# EEG-RM_151117P01.net
KiCad netlist of a schematic drawn in EAGLE
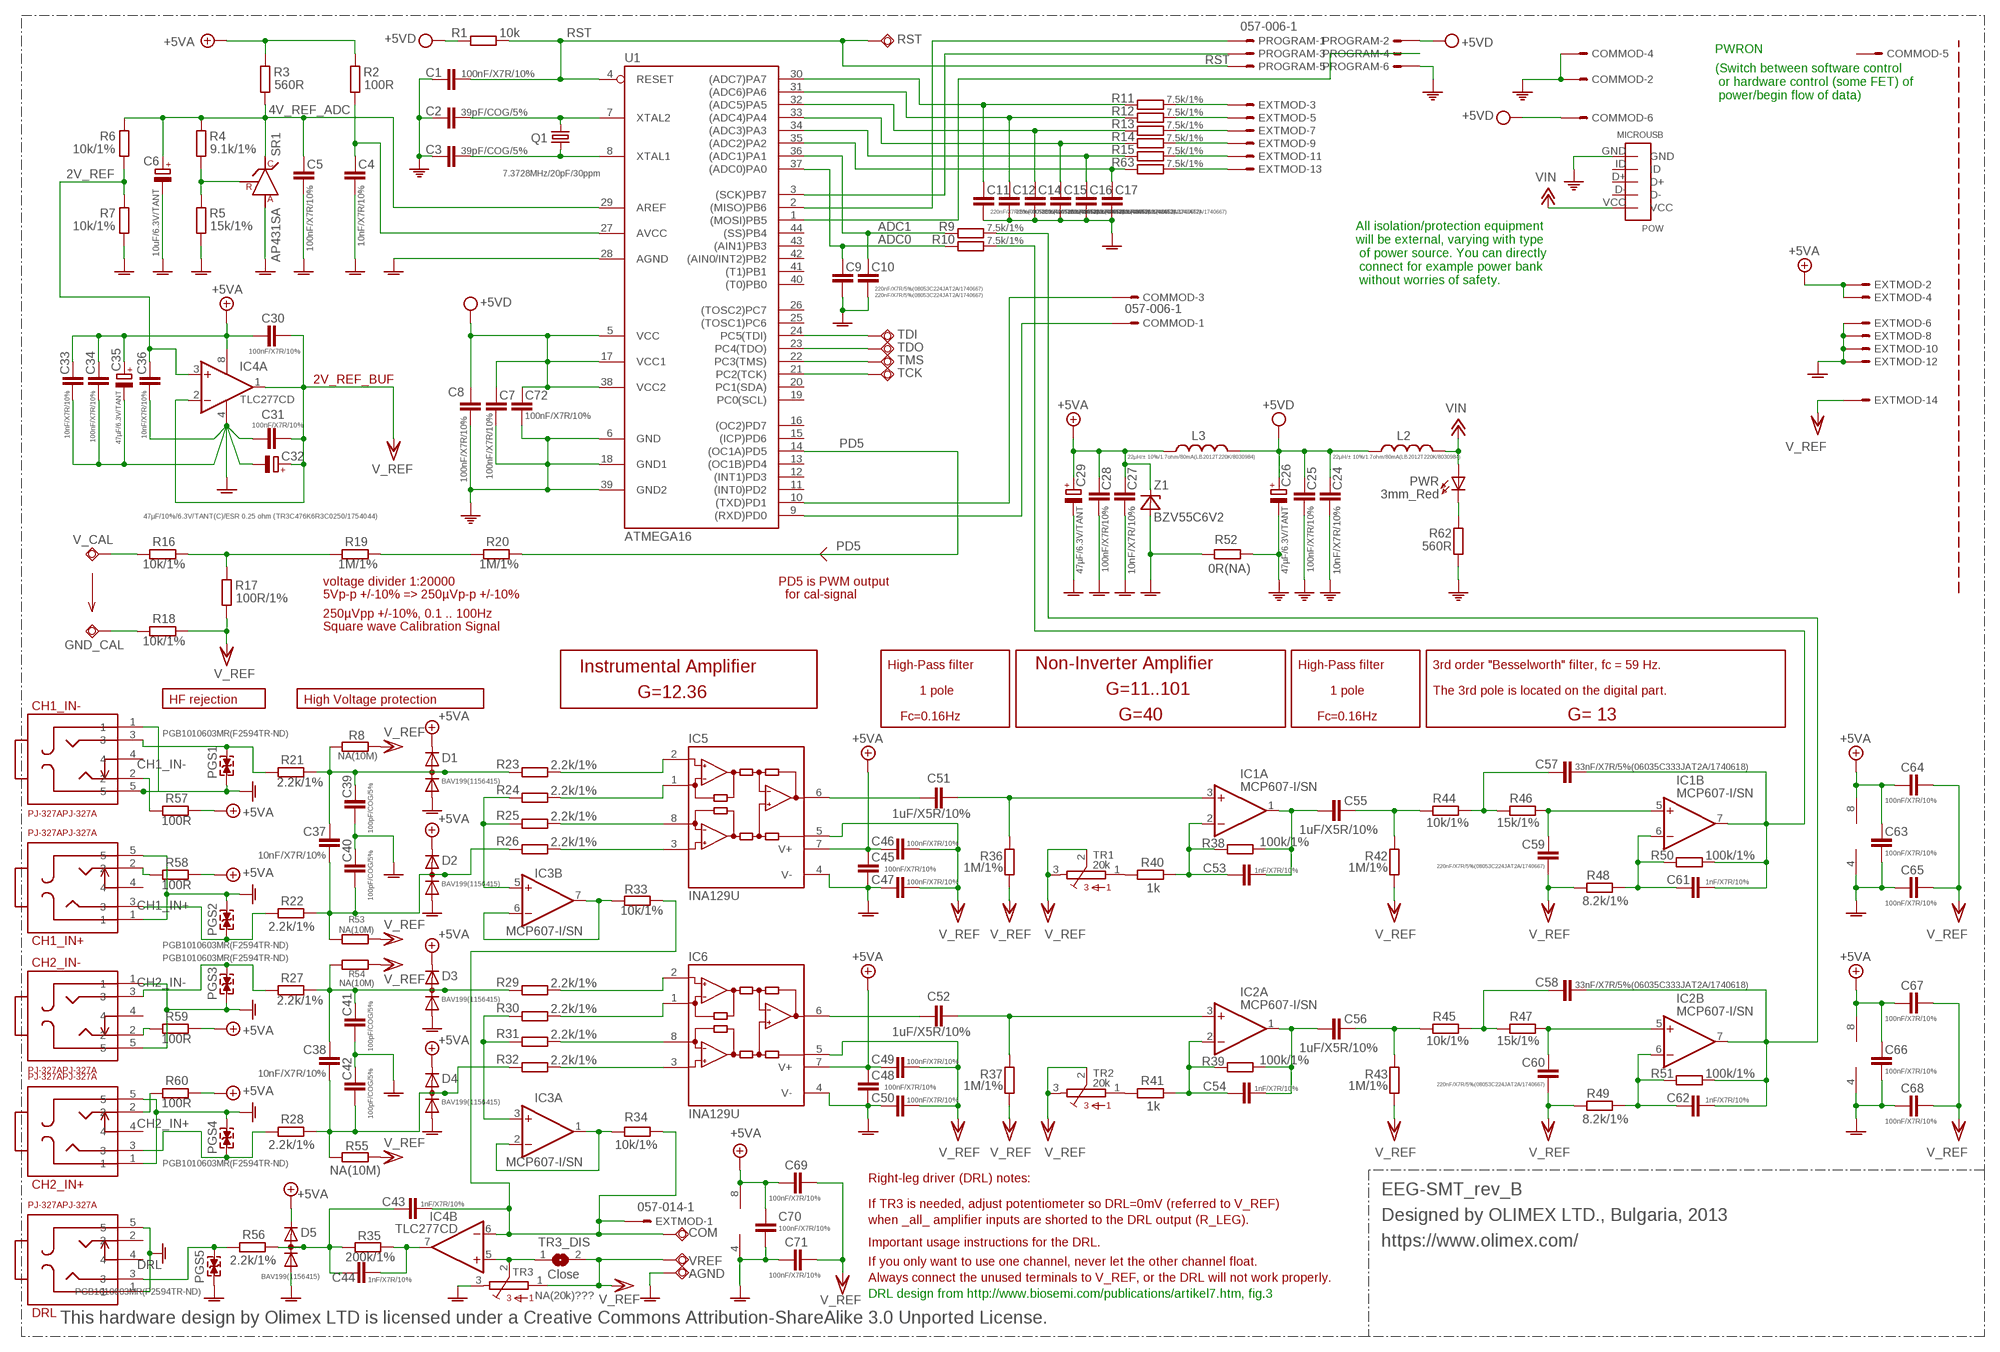
[diagram p0: schematic, sheet 1]

(export (version "E")
  (design (tool "Eeschema 10.0.6"))
  (components
    (comp (ref "AGND")
      (value "TESTPAD3")
      (footprint "eagle-import:TEST_PAD40_70_SQUARE")
      (libsource (lib "eagle-import") (part "TESTPAD3"))
    )
    (comp (ref "C1")
      (value "100nF/X7R/10%")
      (footprint "eagle-import:C2012")
      (libsource (lib "eagle-import") (part "C-EUC2012"))
    )
    (comp (ref "C2")
      (value "39pF/COG/5%")
      (footprint "eagle-import:C2012")
      (libsource (lib "eagle-import") (part "C-EUC2012"))
    )
    (comp (ref "C3")
      (value "39pF/COG/5%")
      (footprint "eagle-import:C2012")
      (libsource (lib "eagle-import") (part "C-EUC2012"))
    )
    (comp (ref "C4")
      (value "10nF/X7R/10%")
      (footprint "eagle-import:C2012")
      (libsource (lib "eagle-import") (part "C-EUC2012"))
    )
    (comp (ref "C5")
      (value "100nF/X7R/10%")
      (footprint "eagle-import:C2012")
      (libsource (lib "eagle-import") (part "C-EUC2012"))
    )
    (comp (ref "C6")
      (value "10uF/6.3V/TANT")
      (footprint "eagle-import:CT3216")
      (libsource (lib "eagle-import") (part "CPOL-EUCT3216"))
    )
    (comp (ref "C7")
      (value "100nF/X7R/10%")
      (footprint "eagle-import:C2012")
      (libsource (lib "eagle-import") (part "C-EUC2012"))
    )
    (comp (ref "C8")
      (value "100nF/X7R/10%")
      (footprint "eagle-import:C2012")
      (libsource (lib "eagle-import") (part "C-EUC2012"))
    )
    (comp (ref "C9")
      (value "220nF/X7R/5%(08053C224JAT2A/1740667)")
      (footprint "eagle-import:C2012")
      (libsource (lib "eagle-import") (part "C-EUC2012"))
    )
    (comp (ref "C10")
      (value "220nF/X7R/5%(08053C224JAT2A/1740667)")
      (footprint "eagle-import:C2012")
      (libsource (lib "eagle-import") (part "C-EUC2012"))
    )
    (comp (ref "C11")
      (value "220nF/X7R/5%(08053C224JAT2A/1740667)")
      (footprint "eagle-import:C2012")
      (libsource (lib "eagle-import") (part "C-EUC2012"))
    )
    (comp (ref "C12")
      (value "220nF/X7R/5%(08053C224JAT2A/1740667)")
      (footprint "eagle-import:C2012")
      (libsource (lib "eagle-import") (part "C-EUC2012"))
    )
    (comp (ref "C14")
      (value "220nF/X7R/5%(08053C224JAT2A/1740667)")
      (footprint "eagle-import:C2012")
      (libsource (lib "eagle-import") (part "C-EUC2012"))
    )
    (comp (ref "C15")
      (value "220nF/X7R/5%(08053C224JAT2A/1740667)")
      (footprint "eagle-import:C2012")
      (libsource (lib "eagle-import") (part "C-EUC2012"))
    )
    (comp (ref "C16")
      (value "220nF/X7R/5%(08053C224JAT2A/1740667)")
      (footprint "eagle-import:C2012")
      (libsource (lib "eagle-import") (part "C-EUC2012"))
    )
    (comp (ref "C17")
      (value "220nF/X7R/5%(08053C224JAT2A/1740667)")
      (footprint "eagle-import:C2012")
      (libsource (lib "eagle-import") (part "C-EUC2012"))
    )
    (comp (ref "C24")
      (value "10nF/X7R/10%")
      (footprint "eagle-import:C2012")
      (libsource (lib "eagle-import") (part "C-EUC2012"))
    )
    (comp (ref "C25")
      (value "100nF/X7R/10%")
      (footprint "eagle-import:C2012")
      (libsource (lib "eagle-import") (part "C-EUC2012"))
    )
    (comp (ref "C26")
      (value "47µF/6.3V/TANT")
      (footprint "eagle-import:CT3528")
      (libsource (lib "eagle-import") (part "CPOL-EUCT3528"))
    )
    (comp (ref "C27")
      (value "10nF/X7R/10%")
      (footprint "eagle-import:C2012")
      (libsource (lib "eagle-import") (part "C-EUC2012"))
    )
    (comp (ref "C28")
      (value "100nF/X7R/10%")
      (footprint "eagle-import:C2012")
      (libsource (lib "eagle-import") (part "C-EUC2012"))
    )
    (comp (ref "C29")
      (value "47µF/6.3V/TANT")
      (footprint "eagle-import:CT3528")
      (libsource (lib "eagle-import") (part "CPOL-EUCT3528"))
    )
    (comp (ref "C30")
      (value "100nF/X7R/10%")
      (footprint "eagle-import:C2012")
      (libsource (lib "eagle-import") (part "C-EUC2012"))
    )
    (comp (ref "C31")
      (value "100nF/X7R/10%")
      (footprint "eagle-import:C2012")
      (libsource (lib "eagle-import") (part "C-EUC2012"))
    )
    (comp (ref "C32")
      (value "47µF/10%/6.3V/TANT(C)/ESR 0.25 ohm (TR3C476K6R3C0250/1754044)")
      (footprint "eagle-import:CT6032")
      (libsource (lib "eagle-import") (part "CPOL-EUCT6032"))
    )
    (comp (ref "C33")
      (value "10nF/X7R/10%")
      (footprint "eagle-import:C2012")
      (libsource (lib "eagle-import") (part "C-EUC2012"))
    )
    (comp (ref "C34")
      (value "100nF/X7R/10%")
      (footprint "eagle-import:C2012")
      (libsource (lib "eagle-import") (part "C-EUC2012"))
    )
    (comp (ref "C35")
      (value "47µF/6.3V/TANT")
      (footprint "eagle-import:CT3528")
      (libsource (lib "eagle-import") (part "CPOL-EUCT3528"))
    )
    (comp (ref "C36")
      (value "10nF/X7R/10%")
      (footprint "eagle-import:C2012")
      (libsource (lib "eagle-import") (part "C-EUC2012"))
    )
    (comp (ref "C37")
      (value "10nF/X7R/10%")
      (footprint "eagle-import:C2012")
      (libsource (lib "eagle-import") (part "C-EUC2012"))
    )
    (comp (ref "C38")
      (value "10nF/X7R/10%")
      (footprint "eagle-import:C2012")
      (libsource (lib "eagle-import") (part "C-EUC2012"))
    )
    (comp (ref "C39")
      (value "100pF/COG/5%")
      (footprint "eagle-import:C2012")
      (libsource (lib "eagle-import") (part "C-EUC2012"))
    )
    (comp (ref "C40")
      (value "100pF/COG/5%")
      (footprint "eagle-import:C2012")
      (libsource (lib "eagle-import") (part "C-EUC2012"))
    )
    (comp (ref "C41")
      (value "100pF/COG/5%")
      (footprint "eagle-import:C2012")
      (libsource (lib "eagle-import") (part "C-EUC2012"))
    )
    (comp (ref "C42")
      (value "100pF/COG/5%")
      (footprint "eagle-import:C2012")
      (libsource (lib "eagle-import") (part "C-EUC2012"))
    )
    (comp (ref "C43")
      (value "1nF/X7R/10%")
      (footprint "eagle-import:C2012")
      (libsource (lib "eagle-import") (part "C-EUC2012"))
    )
    (comp (ref "C44")
      (value "1nF/X7R/10%")
      (footprint "eagle-import:C2012")
      (libsource (lib "eagle-import") (part "C-EUC2012"))
    )
    (comp (ref "C45")
      (value "100nF/X7R/10%")
      (footprint "eagle-import:C2012")
      (libsource (lib "eagle-import") (part "C-EUC2012"))
    )
    (comp (ref "C46")
      (value "100nF/X7R/10%")
      (footprint "eagle-import:C2012")
      (libsource (lib "eagle-import") (part "C-EUC2012"))
    )
    (comp (ref "C47")
      (value "100nF/X7R/10%")
      (footprint "eagle-import:C2012")
      (libsource (lib "eagle-import") (part "C-EUC2012"))
    )
    (comp (ref "C48")
      (value "100nF/X7R/10%")
      (footprint "eagle-import:C2012")
      (libsource (lib "eagle-import") (part "C-EUC2012"))
    )
    (comp (ref "C49")
      (value "100nF/X7R/10%")
      (footprint "eagle-import:C2012")
      (libsource (lib "eagle-import") (part "C-EUC2012"))
    )
    (comp (ref "C50")
      (value "100nF/X7R/10%")
      (footprint "eagle-import:C2012")
      (libsource (lib "eagle-import") (part "C-EUC2012"))
    )
    (comp (ref "C51")
      (value "1uF/X5R/10%")
      (footprint "eagle-import:C2012")
      (libsource (lib "eagle-import") (part "C-EUC2012"))
    )
    (comp (ref "C52")
      (value "1uF/X5R/10%")
      (footprint "eagle-import:C2012")
      (libsource (lib "eagle-import") (part "C-EUC2012"))
    )
    (comp (ref "C53")
      (value "1nF/X7R/10%")
      (footprint "eagle-import:C2012")
      (libsource (lib "eagle-import") (part "C-EUC2012"))
    )
    (comp (ref "C54")
      (value "1nF/X7R/10%")
      (footprint "eagle-import:C2012")
      (libsource (lib "eagle-import") (part "C-EUC2012"))
    )
    (comp (ref "C55")
      (value "1uF/X5R/10%")
      (footprint "eagle-import:C2012")
      (libsource (lib "eagle-import") (part "C-EUC2012"))
    )
    (comp (ref "C56")
      (value "1uF/X5R/10%")
      (footprint "eagle-import:C2012")
      (libsource (lib "eagle-import") (part "C-EUC2012"))
    )
    (comp (ref "C57")
      (value "33nF/X7R/5%(06035C333JAT2A/1740618)")
      (footprint "eagle-import:C2012")
      (libsource (lib "eagle-import") (part "C-EUC2012"))
    )
    (comp (ref "C58")
      (value "33nF/X7R/5%(06035C333JAT2A/1740618)")
      (footprint "eagle-import:C2012")
      (libsource (lib "eagle-import") (part "C-EUC2012"))
    )
    (comp (ref "C59")
      (value "220nF/X7R/5%(08053C224JAT2A/1740667)")
      (footprint "eagle-import:C2012")
      (libsource (lib "eagle-import") (part "C-EUC2012"))
    )
    (comp (ref "C60")
      (value "220nF/X7R/5%(08053C224JAT2A/1740667)")
      (footprint "eagle-import:C2012")
      (libsource (lib "eagle-import") (part "C-EUC2012"))
    )
    (comp (ref "C61")
      (value "1nF/X7R/10%")
      (footprint "eagle-import:C2012")
      (libsource (lib "eagle-import") (part "C-EUC2012"))
    )
    (comp (ref "C62")
      (value "1nF/X7R/10%")
      (footprint "eagle-import:C2012")
      (libsource (lib "eagle-import") (part "C-EUC2012"))
    )
    (comp (ref "C63")
      (value "100nF/X7R/10%")
      (footprint "eagle-import:C2012")
      (libsource (lib "eagle-import") (part "C-EUC2012"))
    )
    (comp (ref "C64")
      (value "100nF/X7R/10%")
      (footprint "eagle-import:C2012")
      (libsource (lib "eagle-import") (part "C-EUC2012"))
    )
    (comp (ref "C65")
      (value "100nF/X7R/10%")
      (footprint "eagle-import:C2012")
      (libsource (lib "eagle-import") (part "C-EUC2012"))
    )
    (comp (ref "C66")
      (value "100nF/X7R/10%")
      (footprint "eagle-import:C2012")
      (libsource (lib "eagle-import") (part "C-EUC2012"))
    )
    (comp (ref "C67")
      (value "100nF/X7R/10%")
      (footprint "eagle-import:C2012")
      (libsource (lib "eagle-import") (part "C-EUC2012"))
    )
    (comp (ref "C68")
      (value "100nF/X7R/10%")
      (footprint "eagle-import:C2012")
      (libsource (lib "eagle-import") (part "C-EUC2012"))
    )
    (comp (ref "C69")
      (value "100nF/X7R/10%")
      (footprint "eagle-import:C2012")
      (libsource (lib "eagle-import") (part "C-EUC2012"))
    )
    (comp (ref "C70")
      (value "100nF/X7R/10%")
      (footprint "eagle-import:C2012")
      (libsource (lib "eagle-import") (part "C-EUC2012"))
    )
    (comp (ref "C71")
      (value "100nF/X7R/10%")
      (footprint "eagle-import:C2012")
      (libsource (lib "eagle-import") (part "C-EUC2012"))
    )
    (comp (ref "C72")
      (value "100nF/X7R/10%")
      (footprint "eagle-import:C2012")
      (libsource (lib "eagle-import") (part "C-EUC2012"))
    )
    (comp (ref "CH1_IN+")
      (value "PJ-327APJ-327A")
      (footprint "eagle-import:PJ-327A")
      (libsource (lib "eagle-import") (part "PJ-327APJ-327A"))
    )
    (comp (ref "CH1_IN-")
      (value "PJ-327APJ-327A")
      (footprint "eagle-import:PJ-327A")
      (libsource (lib "eagle-import") (part "PJ-327APJ-327A"))
    )
    (comp (ref "CH2_IN+")
      (value "PJ-327APJ-327A")
      (footprint "eagle-import:PJ-327A")
      (libsource (lib "eagle-import") (part "PJ-327APJ-327A"))
    )
    (comp (ref "CH2_IN-")
      (value "PJ-327APJ-327A")
      (footprint "eagle-import:PJ-327A")
      (libsource (lib "eagle-import") (part "PJ-327APJ-327A"))
    )
    (comp (ref "COM")
      (value "TESTPAD3")
      (footprint "eagle-import:TEST_PAD40_70_SQUARE")
      (libsource (lib "eagle-import") (part "TESTPAD3"))
    )
    (comp (ref "COMMOD")
      (value "057-006-1")
      (footprint "eagle-import:057-006-1")
      (libsource (lib "eagle-import") (part "057-006-1"))
    )
    (comp (ref "D1")
      (value "BAV199(1156415)")
      (footprint "eagle-import:SOT23C(BAT54S)")
      (libsource (lib "eagle-import") (part "DIODE_AC-AC_"))
    )
    (comp (ref "D2")
      (value "BAV199(1156415)")
      (footprint "eagle-import:SOT23C(BAT54S)")
      (libsource (lib "eagle-import") (part "DIODE_AC-AC_"))
    )
    (comp (ref "D3")
      (value "BAV199(1156415)")
      (footprint "eagle-import:SOT23C(BAT54S)")
      (libsource (lib "eagle-import") (part "DIODE_AC-AC_"))
    )
    (comp (ref "D4")
      (value "BAV199(1156415)")
      (footprint "eagle-import:SOT23C(BAT54S)")
      (libsource (lib "eagle-import") (part "DIODE_AC-AC_"))
    )
    (comp (ref "D5")
      (value "BAV199(1156415)")
      (footprint "eagle-import:SOT23C(BAT54S)")
      (libsource (lib "eagle-import") (part "DIODE_AC-AC_"))
    )
    (comp (ref "DRL")
      (value "PJ-327APJ-327A")
      (footprint "eagle-import:PJ-327A")
      (libsource (lib "eagle-import") (part "PJ-327APJ-327A"))
    )
    (comp (ref "EXTMOD")
      (value "057-014-1")
      (footprint "eagle-import:057-014-1")
      (libsource (lib "eagle-import") (part "057-014-1"))
    )
    (comp (ref "GND_CAL")
      (value "TESTPAD3")
      (footprint "eagle-import:TEST_PAD40_70_SQUARE")
      (libsource (lib "eagle-import") (part "TESTPAD3"))
    )
    (comp (ref "IC1")
      (value "MCP607-I/SN")
      (footprint "eagle-import:SO08")
      (libsource (lib "eagle-import") (part "LM358D"))
    )
    (comp (ref "IC2")
      (value "MCP607-I/SN")
      (footprint "eagle-import:SO08")
      (libsource (lib "eagle-import") (part "LM358D"))
    )
    (comp (ref "IC3")
      (value "MCP607-I/SN")
      (footprint "eagle-import:SO08")
      (libsource (lib "eagle-import") (part "LM358D"))
    )
    (comp (ref "IC4")
      (value "TLC277CD")
      (footprint "eagle-import:SO08")
      (libsource (lib "eagle-import") (part "LM358D"))
    )
    (comp (ref "IC5")
      (value "INA129U")
      (footprint "eagle-import:SO08")
      (fields (field (name "MF") "TEXAS INSTRUMENTS"))
      (libsource (lib "eagle-import") (part "INA129U"))
    )
    (comp (ref "IC6")
      (value "INA129U")
      (footprint "eagle-import:SO08")
      (fields (field (name "MF") "TEXAS INSTRUMENTS"))
      (libsource (lib "eagle-import") (part "INA129U"))
    )
    (comp (ref "L2")
      (value "22µH/± 10%/1.7ohm/80mA(LB2012T220K/8030984)")
      (footprint "eagle-import:L2012C")
      (libsource (lib "eagle-import") (part "L-USL2012C"))
    )
    (comp (ref "L3")
      (value "22µH/± 10%/1.7ohm/80mA(LB2012T220K/8030984)")
      (footprint "eagle-import:L2012C")
      (libsource (lib "eagle-import") (part "L-USL2012C"))
    )
    (comp (ref "PGS1")
      (value "PGB1010603MR(F2594TR-ND)")
      (footprint "eagle-import:0603")
      (libsource (lib "eagle-import") (part "PGB1010603MR(F2594TR-ND)"))
    )
    (comp (ref "PGS2")
      (value "PGB1010603MR(F2594TR-ND)")
      (footprint "eagle-import:0603")
      (libsource (lib "eagle-import") (part "PGB1010603MR(F2594TR-ND)"))
    )
    (comp (ref "PGS3")
      (value "PGB1010603MR(F2594TR-ND)")
      (footprint "eagle-import:0603")
      (libsource (lib "eagle-import") (part "PGB1010603MR(F2594TR-ND)"))
    )
    (comp (ref "PGS4")
      (value "PGB1010603MR(F2594TR-ND)")
      (footprint "eagle-import:0603")
      (libsource (lib "eagle-import") (part "PGB1010603MR(F2594TR-ND)"))
    )
    (comp (ref "PGS5")
      (value "PGB1010603MR(F2594TR-ND)")
      (footprint "eagle-import:0603")
      (libsource (lib "eagle-import") (part "PGB1010603MR(F2594TR-ND)"))
    )
    (comp (ref "POW")
      (value "MICROUSB")
      (footprint "eagle-import:MICROUSB")
      (libsource (lib "eagle-import") (part "MICROUSB"))
    )
    (comp (ref "PROGRAM")
      (value "057-006-1")
      (footprint "eagle-import:057-006-1")
      (libsource (lib "eagle-import") (part "057-006-1"))
    )
    (comp (ref "PWR")
      (value "3mm_Red")
      (footprint "eagle-import:LED-3.0MM")
      (libsource (lib "eagle-import") (part "LED3.0MM"))
    )
    (comp (ref "Q1")
      (value "7.3728MHz/20pF/30ppm")
      (footprint "eagle-import:HC49_SMD2_THIN")
      (libsource (lib "eagle-import") (part "HC49/S1"))
    )
    (comp (ref "R1")
      (value "10k")
      (footprint "eagle-import:M2012")
      (libsource (lib "eagle-import") (part "R-EU_M2012"))
    )
    (comp (ref "R2")
      (value "100R")
      (footprint "eagle-import:M2012")
      (libsource (lib "eagle-import") (part "R-EU_M2012"))
    )
    (comp (ref "R3")
      (value "560R")
      (footprint "eagle-import:M2012")
      (libsource (lib "eagle-import") (part "R-EU_M2012"))
    )
    (comp (ref "R4")
      (value "9.1k/1%")
      (footprint "eagle-import:M2012")
      (libsource (lib "eagle-import") (part "R-EU_M2012"))
    )
    (comp (ref "R5")
      (value "15k/1%")
      (footprint "eagle-import:M2012")
      (libsource (lib "eagle-import") (part "R-EU_M2012"))
    )
    (comp (ref "R6")
      (value "10k/1%")
      (footprint "eagle-import:M2012")
      (libsource (lib "eagle-import") (part "R-EU_M2012"))
    )
    (comp (ref "R7")
      (value "10k/1%")
      (footprint "eagle-import:M2012")
      (libsource (lib "eagle-import") (part "R-EU_M2012"))
    )
    (comp (ref "R8")
      (value "NA(10M)")
      (footprint "eagle-import:M2012")
      (libsource (lib "eagle-import") (part "R-EU_M2012"))
    )
    (comp (ref "R9")
      (value "7.5k/1%")
      (footprint "eagle-import:M2012")
      (libsource (lib "eagle-import") (part "R-EU_M2012"))
    )
    (comp (ref "R10")
      (value "7.5k/1%")
      (footprint "eagle-import:M2012")
      (libsource (lib "eagle-import") (part "R-EU_M2012"))
    )
    (comp (ref "R11")
      (value "7.5k/1%")
      (footprint "eagle-import:M2012")
      (libsource (lib "eagle-import") (part "R-EU_M2012"))
    )
    (comp (ref "R12")
      (value "7.5k/1%")
      (footprint "eagle-import:M2012")
      (libsource (lib "eagle-import") (part "R-EU_M2012"))
    )
    (comp (ref "R13")
      (value "7.5k/1%")
      (footprint "eagle-import:M2012")
      (libsource (lib "eagle-import") (part "R-EU_M2012"))
    )
    (comp (ref "R14")
      (value "7.5k/1%")
      (footprint "eagle-import:M2012")
      (libsource (lib "eagle-import") (part "R-EU_M2012"))
    )
    (comp (ref "R15")
      (value "7.5k/1%")
      (footprint "eagle-import:M2012")
      (libsource (lib "eagle-import") (part "R-EU_M2012"))
    )
    (comp (ref "R16")
      (value "10k/1%")
      (footprint "eagle-import:M2012")
      (libsource (lib "eagle-import") (part "R-EU_M2012"))
    )
    (comp (ref "R17")
      (value "100R/1%")
      (footprint "eagle-import:M2012")
      (libsource (lib "eagle-import") (part "R-EU_M2012"))
    )
    (comp (ref "R18")
      (value "10k/1%")
      (footprint "eagle-import:M2012")
      (libsource (lib "eagle-import") (part "R-EU_M2012"))
    )
    (comp (ref "R19")
      (value "1M/1%")
      (footprint "eagle-import:M2012")
      (libsource (lib "eagle-import") (part "R-EU_M2012"))
    )
    (comp (ref "R20")
      (value "1M/1%")
      (footprint "eagle-import:M2012")
      (libsource (lib "eagle-import") (part "R-EU_M2012"))
    )
    (comp (ref "R21")
      (value "2.2k/1%")
      (footprint "eagle-import:M2012")
      (libsource (lib "eagle-import") (part "R-EU_M2012"))
    )
    (comp (ref "R22")
      (value "2.2k/1%")
      (footprint "eagle-import:M2012")
      (libsource (lib "eagle-import") (part "R-EU_M2012"))
    )
    (comp (ref "R23")
      (value "2.2k/1%")
      (footprint "eagle-import:M2012")
      (libsource (lib "eagle-import") (part "R-EU_M2012"))
    )
    (comp (ref "R24")
      (value "2.2k/1%")
      (footprint "eagle-import:M2012")
      (libsource (lib "eagle-import") (part "R-EU_M2012"))
    )
    (comp (ref "R25")
      (value "2.2k/1%")
      (footprint "eagle-import:M2012")
      (libsource (lib "eagle-import") (part "R-EU_M2012"))
    )
    (comp (ref "R26")
      (value "2.2k/1%")
      (footprint "eagle-import:M2012")
      (libsource (lib "eagle-import") (part "R-EU_M2012"))
    )
    (comp (ref "R27")
      (value "2.2k/1%")
      (footprint "eagle-import:M2012")
      (libsource (lib "eagle-import") (part "R-EU_M2012"))
    )
    (comp (ref "R28")
      (value "2.2k/1%")
      (footprint "eagle-import:M2012")
      (libsource (lib "eagle-import") (part "R-EU_M2012"))
    )
    (comp (ref "R29")
      (value "2.2k/1%")
      (footprint "eagle-import:M2012")
      (libsource (lib "eagle-import") (part "R-EU_M2012"))
    )
    (comp (ref "R30")
      (value "2.2k/1%")
      (footprint "eagle-import:M2012")
      (libsource (lib "eagle-import") (part "R-EU_M2012"))
    )
    (comp (ref "R31")
      (value "2.2k/1%")
      (footprint "eagle-import:M2012")
      (libsource (lib "eagle-import") (part "R-EU_M2012"))
    )
    (comp (ref "R32")
      (value "2.2k/1%")
      (footprint "eagle-import:M2012")
      (libsource (lib "eagle-import") (part "R-EU_M2012"))
    )
    (comp (ref "R33")
      (value "10k/1%")
      (footprint "eagle-import:M2012")
      (libsource (lib "eagle-import") (part "R-EU_M2012"))
    )
    (comp (ref "R34")
      (value "10k/1%")
      (footprint "eagle-import:M2012")
      (libsource (lib "eagle-import") (part "R-EU_M2012"))
    )
    (comp (ref "R35")
      (value "200k/1%")
      (footprint "eagle-import:M2012")
      (libsource (lib "eagle-import") (part "R-EU_M2012"))
    )
    (comp (ref "R36")
      (value "1M/1%")
      (footprint "eagle-import:M2012")
      (libsource (lib "eagle-import") (part "R-EU_M2012"))
    )
    (comp (ref "R37")
      (value "1M/1%")
      (footprint "eagle-import:M2012")
      (libsource (lib "eagle-import") (part "R-EU_M2012"))
    )
    (comp (ref "R38")
      (value "100k/1%")
      (footprint "eagle-import:M2012")
      (libsource (lib "eagle-import") (part "R-EU_M2012"))
    )
    (comp (ref "R39")
      (value "100k/1%")
      (footprint "eagle-import:M2012")
      (libsource (lib "eagle-import") (part "R-EU_M2012"))
    )
    (comp (ref "R40")
      (value "1k")
      (footprint "eagle-import:M2012")
      (libsource (lib "eagle-import") (part "R-EU_M2012"))
    )
    (comp (ref "R41")
      (value "1k")
      (footprint "eagle-import:M2012")
      (libsource (lib "eagle-import") (part "R-EU_M2012"))
    )
    (comp (ref "R42")
      (value "1M/1%")
      (footprint "eagle-import:M2012")
      (libsource (lib "eagle-import") (part "R-EU_M2012"))
    )
    (comp (ref "R43")
      (value "1M/1%")
      (footprint "eagle-import:M2012")
      (libsource (lib "eagle-import") (part "R-EU_M2012"))
    )
    (comp (ref "R44")
      (value "10k/1%")
      (footprint "eagle-import:M2012")
      (libsource (lib "eagle-import") (part "R-EU_M2012"))
    )
    (comp (ref "R45")
      (value "10k/1%")
      (footprint "eagle-import:M2012")
      (libsource (lib "eagle-import") (part "R-EU_M2012"))
    )
    (comp (ref "R46")
      (value "15k/1%")
      (footprint "eagle-import:M2012")
      (libsource (lib "eagle-import") (part "R-EU_M2012"))
    )
    (comp (ref "R47")
      (value "15k/1%")
      (footprint "eagle-import:M2012")
      (libsource (lib "eagle-import") (part "R-EU_M2012"))
    )
    (comp (ref "R48")
      (value "8.2k/1%")
      (footprint "eagle-import:M2012")
      (libsource (lib "eagle-import") (part "R-EU_M2012"))
    )
    (comp (ref "R49")
      (value "8.2k/1%")
      (footprint "eagle-import:M2012")
      (libsource (lib "eagle-import") (part "R-EU_M2012"))
    )
    (comp (ref "R50")
      (value "100k/1%")
      (footprint "eagle-import:M2012")
      (libsource (lib "eagle-import") (part "R-EU_M2012"))
    )
    (comp (ref "R51")
      (value "100k/1%")
      (footprint "eagle-import:M2012")
      (libsource (lib "eagle-import") (part "R-EU_M2012"))
    )
    (comp (ref "R52")
      (value "0R(NA)")
      (footprint "eagle-import:M2012")
      (libsource (lib "eagle-import") (part "R-EU_M2012"))
    )
    (comp (ref "R53")
      (value "NA(10M)")
      (footprint "eagle-import:M2012")
      (libsource (lib "eagle-import") (part "R-EU_M2012"))
    )
    (comp (ref "R54")
      (value "NA(10M)")
      (footprint "eagle-import:M2012")
      (libsource (lib "eagle-import") (part "R-EU_M2012"))
    )
    (comp (ref "R55")
      (value "NA(10M)")
      (footprint "eagle-import:M2012")
      (libsource (lib "eagle-import") (part "R-EU_M2012"))
    )
    (comp (ref "R56")
      (value "2.2k/1%")
      (footprint "eagle-import:M2012")
      (libsource (lib "eagle-import") (part "R-EU_M2012"))
    )
    (comp (ref "R57")
      (value "100R")
      (footprint "eagle-import:M2012")
      (libsource (lib "eagle-import") (part "R-EU_M2012"))
    )
    (comp (ref "R58")
      (value "100R")
      (footprint "eagle-import:M2012")
      (libsource (lib "eagle-import") (part "R-EU_M2012"))
    )
    (comp (ref "R59")
      (value "100R")
      (footprint "eagle-import:M2012")
      (libsource (lib "eagle-import") (part "R-EU_M2012"))
    )
    (comp (ref "R60")
      (value "100R")
      (footprint "eagle-import:M2012")
      (libsource (lib "eagle-import") (part "R-EU_M2012"))
    )
    (comp (ref "R62")
      (value "560R")
      (footprint "eagle-import:M2012")
      (libsource (lib "eagle-import") (part "R-EU_M2012"))
    )
    (comp (ref "R63")
      (value "7.5k/1%")
      (footprint "eagle-import:M2012")
      (libsource (lib "eagle-import") (part "R-EU_M2012"))
    )
    (comp (ref "RST")
      (value "TESTPAD80/30")
      (footprint "eagle-import:SMD80_30")
      (libsource (lib "eagle-import") (part "TESTPAD80/30"))
    )
    (comp (ref "SR1")
      (value "AP431SA")
      (footprint "eagle-import:SOT-23")
      (libsource (lib "eagle-import") (part "TL431'''"))
    )
    (comp (ref "TCK")
      (value "TESTPAD80/30")
      (footprint "eagle-import:SMD80_30")
      (libsource (lib "eagle-import") (part "TESTPAD80/30"))
    )
    (comp (ref "TDI")
      (value "TESTPAD80/30")
      (footprint "eagle-import:SMD80_30")
      (libsource (lib "eagle-import") (part "TESTPAD80/30"))
    )
    (comp (ref "TDO")
      (value "TESTPAD80/30")
      (footprint "eagle-import:SMD80_30")
      (libsource (lib "eagle-import") (part "TESTPAD80/30"))
    )
    (comp (ref "TMS")
      (value "TESTPAD80/30")
      (footprint "eagle-import:SMD80_30")
      (libsource (lib "eagle-import") (part "TESTPAD80/30"))
    )
    (comp (ref "TR1")
      (value "20k")
      (footprint "eagle-import:S64Y")
      (libsource (lib "eagle-import") (part "S64Y"))
    )
    (comp (ref "TR2")
      (value "20k")
      (footprint "eagle-import:S64Y")
      (libsource (lib "eagle-import") (part "S64Y"))
    )
    (comp (ref "TR3")
      (value "NA(20k)???")
      (footprint "eagle-import:S64Y")
      (libsource (lib "eagle-import") (part "S64Y"))
    )
    (comp (ref "TR3_DIS")
      (value "Close")
      (footprint "eagle-import:SJ_1_SMALLER")
      (libsource (lib "eagle-import") (part "SJSJ_SMALLER"))
    )
    (comp (ref "U1")
      (value "ATMEGA16")
      (footprint "eagle-import:44TQFP")
      (libsource (lib "eagle-import") (part "ATMEGA16"))
    )
    (comp (ref "VREF")
      (value "TESTPAD3")
      (footprint "eagle-import:TEST_PAD40_70_SQUARE")
      (libsource (lib "eagle-import") (part "TESTPAD3"))
    )
    (comp (ref "V_CAL")
      (value "TESTPAD3")
      (footprint "eagle-import:TEST_PAD40_70_SQUARE")
      (libsource (lib "eagle-import") (part "TESTPAD3"))
    )
    (comp (ref "Z1")
      (value "BZV55C6V2")
      (footprint "eagle-import:MINI-MELF")
      (libsource (lib "eagle-import") (part "ZDIOD-SMD"))
    )
  )
  (nets
    (net (code "1") (name "+5VA") (class "Default")
      (node (ref "C27") (pin "1") (pinfunction "1_1") (pintype "passive"))
      (node (ref "C28") (pin "1") (pinfunction "1_1") (pintype "passive"))
      (node (ref "C29") (pin "+") (pinfunction "+_+") (pintype "passive"))
      (node (ref "C30") (pin "2") (pinfunction "2_2") (pintype "passive"))
      (node (ref "C33") (pin "1") (pinfunction "1_1") (pintype "passive"))
      (node (ref "C34") (pin "1") (pinfunction "1_1") (pintype "passive"))
      (node (ref "C35") (pin "+") (pinfunction "+_+") (pintype "passive"))
      (node (ref "C45") (pin "1") (pinfunction "1_1") (pintype "passive"))
      (node (ref "C46") (pin "1") (pinfunction "1_1") (pintype "passive"))
      (node (ref "C48") (pin "1") (pinfunction "1_1") (pintype "passive"))
      (node (ref "C49") (pin "1") (pinfunction "1_1") (pintype "passive"))
      (node (ref "C63") (pin "1") (pinfunction "1_1") (pintype "passive"))
      (node (ref "C64") (pin "1") (pinfunction "1_1") (pintype "passive"))
      (node (ref "C66") (pin "1") (pinfunction "1_1") (pintype "passive"))
      (node (ref "C67") (pin "1") (pinfunction "1_1") (pintype "passive"))
      (node (ref "C69") (pin "1") (pinfunction "1_1") (pintype "passive"))
      (node (ref "C70") (pin "1") (pinfunction "1_1") (pintype "passive"))
      (node (ref "D1") (pin "2") (pinfunction "K_2") (pintype "passive"))
      (node (ref "D2") (pin "2") (pinfunction "K_2") (pintype "passive"))
      (node (ref "D3") (pin "2") (pinfunction "K_2") (pintype "passive"))
      (node (ref "D4") (pin "2") (pinfunction "K_2") (pintype "passive"))
      (node (ref "D5") (pin "2") (pinfunction "K_2") (pintype "passive"))
      (node (ref "EXTMOD") (pin "2") (pinfunction "S_2") (pintype "passive"))
      (node (ref "EXTMOD") (pin "4") (pinfunction "S_4") (pintype "passive"))
      (node (ref "IC1") (pin "8") (pinfunction "V+_8") (pintype "power_in"))
      (node (ref "IC2") (pin "8") (pinfunction "V+_8") (pintype "power_in"))
      (node (ref "IC3") (pin "8") (pinfunction "V+_8") (pintype "power_in"))
      (node (ref "IC4") (pin "8") (pinfunction "V+_8") (pintype "power_in"))
      (node (ref "IC5") (pin "7") (pinfunction "V+_7") (pintype "power_in"))
      (node (ref "IC6") (pin "7") (pinfunction "V+_7") (pintype "power_in"))
      (node (ref "L3") (pin "2") (pinfunction "2_2") (pintype "passive"))
      (node (ref "R2") (pin "2") (pinfunction "2_2") (pintype "passive"))
      (node (ref "R3") (pin "2") (pinfunction "2_2") (pintype "passive"))
      (node (ref "R57") (pin "2") (pinfunction "2_2") (pintype "passive"))
      (node (ref "R58") (pin "2") (pinfunction "2_2") (pintype "passive"))
      (node (ref "R59") (pin "2") (pinfunction "2_2") (pintype "passive"))
      (node (ref "R60") (pin "2") (pinfunction "2_2") (pintype "passive"))
      (node (ref "Z1") (pin "1") (pinfunction "C_1") (pintype "passive"))
    )
    (net (code "2") (name "+5VD") (class "Default")
      (node (ref "C24") (pin "1") (pinfunction "1_1") (pintype "passive"))
      (node (ref "C25") (pin "1") (pinfunction "1_1") (pintype "passive"))
      (node (ref "C26") (pin "+") (pinfunction "+_+") (pintype "passive"))
      (node (ref "C7") (pin "1") (pinfunction "1_1") (pintype "passive"))
      (node (ref "C72") (pin "1") (pinfunction "1_1") (pintype "passive"))
      (node (ref "C8") (pin "1") (pinfunction "1_1") (pintype "passive"))
      (node (ref "COMMOD") (pin "6") (pinfunction "S_6") (pintype "passive"))
      (node (ref "L2") (pin "2") (pinfunction "2_2") (pintype "passive"))
      (node (ref "L3") (pin "1") (pinfunction "1_1") (pintype "passive"))
      (node (ref "PROGRAM") (pin "2") (pinfunction "S_2") (pintype "passive"))
      (node (ref "R1") (pin "1") (pinfunction "1_1") (pintype "passive"))
      (node (ref "U1") (pin "17") (pinfunction "VCC1_17") (pintype "bidirectional"))
      (node (ref "U1") (pin "38") (pinfunction "VCC2_38") (pintype "bidirectional"))
      (node (ref "U1") (pin "5") (pinfunction "VCC_5") (pintype "power_in"))
    )
    (net (code "3") (name "/2V_REF") (class "Default")
      (node (ref "C36") (pin "1") (pinfunction "1_1") (pintype "passive"))
      (node (ref "IC4") (pin "3") (pinfunction "+IN_3") (pintype "input"))
      (node (ref "R6") (pin "1") (pinfunction "1_1") (pintype "passive"))
      (node (ref "R7") (pin "2") (pinfunction "2_2") (pintype "passive"))
    )
    (net (code "4") (name "/4V_REF_ADC") (class "Default")
      (node (ref "C5") (pin "1") (pinfunction "1_1") (pintype "passive"))
      (node (ref "C6") (pin "+") (pinfunction "+_+") (pintype "passive"))
      (node (ref "R3") (pin "1") (pinfunction "1_1") (pintype "passive"))
      (node (ref "R4") (pin "2") (pinfunction "2_2") (pintype "passive"))
      (node (ref "R6") (pin "2") (pinfunction "2_2") (pintype "passive"))
      (node (ref "SR1") (pin "1") (pinfunction "C_1") (pintype "input"))
      (node (ref "U1") (pin "29") (pinfunction "AREF_29") (pintype "power_in"))
    )
    (net (code "5") (name "/ADC0") (class "Default")
      (node (ref "C9") (pin "1") (pinfunction "1_1") (pintype "passive"))
      (node (ref "R10") (pin "1") (pinfunction "1_1") (pintype "passive"))
      (node (ref "U1") (pin "37") (pinfunction "(ADC0)PA0_37") (pintype "bidirectional"))
    )
    (net (code "6") (name "/ADC1") (class "Default")
      (node (ref "C10") (pin "1") (pinfunction "1_1") (pintype "passive"))
      (node (ref "R9") (pin "1") (pinfunction "1_1") (pintype "passive"))
      (node (ref "U1") (pin "36") (pinfunction "(ADC1)PA1_36") (pintype "bidirectional"))
    )
    (net (code "7") (name "/CH1_IN+") (class "Default")
      (node (ref "CH1_IN+") (pin "3") (pinfunction "3_3") (pintype "bidirectional"))
      (node (ref "PGS2") (pin "1") (pinfunction "1_1") (pintype "input"))
      (node (ref "R22") (pin "1") (pinfunction "1_1") (pintype "passive"))
    )
    (net (code "8") (name "/CH1_IN-") (class "Default")
      (node (ref "CH1_IN-") (pin "3") (pinfunction "3_3") (pintype "bidirectional"))
      (node (ref "PGS1") (pin "2") (pinfunction "2_2") (pintype "input"))
      (node (ref "R21") (pin "1") (pinfunction "1_1") (pintype "passive"))
    )
    (net (code "9") (name "/CH2_IN+") (class "Default")
      (node (ref "CH2_IN+") (pin "3") (pinfunction "3_3") (pintype "bidirectional"))
      (node (ref "PGS4") (pin "1") (pinfunction "1_1") (pintype "input"))
      (node (ref "R28") (pin "1") (pinfunction "1_1") (pintype "passive"))
    )
    (net (code "10") (name "/CH2_IN-") (class "Default")
      (node (ref "CH2_IN-") (pin "3") (pinfunction "3_3") (pintype "bidirectional"))
      (node (ref "PGS3") (pin "2") (pinfunction "2_2") (pintype "input"))
      (node (ref "R27") (pin "1") (pinfunction "1_1") (pintype "passive"))
    )
    (net (code "11") (name "/DRL") (class "Default")
      (node (ref "DRL") (pin "3") (pinfunction "3_3") (pintype "bidirectional"))
      (node (ref "PGS5") (pin "2") (pinfunction "2_2") (pintype "input"))
      (node (ref "R56") (pin "1") (pinfunction "1_1") (pintype "passive"))
    )
    (net (code "12") (name "/PD5") (class "Default")
      (node (ref "R20") (pin "2") (pinfunction "2_2") (pintype "passive"))
      (node (ref "U1") (pin "14") (pinfunction "(OC1A)PD5_14") (pintype "bidirectional"))
    )
    (net (code "13") (name "/RST") (class "Default")
      (node (ref "C1") (pin "1") (pinfunction "1_1") (pintype "passive"))
      (node (ref "PROGRAM") (pin "5") (pinfunction "S_5") (pintype "passive"))
      (node (ref "R1") (pin "2") (pinfunction "2_2") (pintype "passive"))
      (node (ref "RST") (pin "P$1") (pinfunction "PP_P$1") (pintype "passive"))
      (node (ref "U1") (pin "4") (pinfunction "RESET_4") (pintype "input"))
    )
    (net (code "14") (name "GNDA") (class "Default")
      (node (ref "AGND") (pin "P$1") (pinfunction "PP_P$1") (pintype "passive"))
      (node (ref "C10") (pin "2") (pinfunction "2_2") (pintype "passive"))
      (node (ref "C11") (pin "2") (pinfunction "2_2") (pintype "passive"))
      (node (ref "C12") (pin "2") (pinfunction "2_2") (pintype "passive"))
      (node (ref "C14") (pin "2") (pinfunction "2_2") (pintype "passive"))
      (node (ref "C15") (pin "2") (pinfunction "2_2") (pintype "passive"))
      (node (ref "C16") (pin "2") (pinfunction "2_2") (pintype "passive"))
      (node (ref "C17") (pin "2") (pinfunction "2_2") (pintype "passive"))
      (node (ref "C27") (pin "2") (pinfunction "2_2") (pintype "passive"))
      (node (ref "C28") (pin "2") (pinfunction "2_2") (pintype "passive"))
      (node (ref "C29") (pin "-") (pinfunction "-_-") (pintype "passive"))
      (node (ref "C31") (pin "2") (pinfunction "2_2") (pintype "passive"))
      (node (ref "C32") (pin "-") (pinfunction "-_-") (pintype "passive"))
      (node (ref "C33") (pin "2") (pinfunction "2_2") (pintype "passive"))
      (node (ref "C34") (pin "2") (pinfunction "2_2") (pintype "passive"))
      (node (ref "C35") (pin "-") (pinfunction "-_-") (pintype "passive"))
      (node (ref "C36") (pin "2") (pinfunction "2_2") (pintype "passive"))
      (node (ref "C39") (pin "1") (pinfunction "1_1") (pintype "passive"))
      (node (ref "C4") (pin "2") (pinfunction "2_2") (pintype "passive"))
      (node (ref "C40") (pin "2") (pinfunction "2_2") (pintype "passive"))
      (node (ref "C41") (pin "1") (pinfunction "1_1") (pintype "passive"))
      (node (ref "C42") (pin "2") (pinfunction "2_2") (pintype "passive"))
      (node (ref "C45") (pin "2") (pinfunction "2_2") (pintype "passive"))
      (node (ref "C47") (pin "1") (pinfunction "1_1") (pintype "passive"))
      (node (ref "C48") (pin "2") (pinfunction "2_2") (pintype "passive"))
      (node (ref "C5") (pin "2") (pinfunction "2_2") (pintype "passive"))
      (node (ref "C50") (pin "1") (pinfunction "1_1") (pintype "passive"))
      (node (ref "C6") (pin "-") (pinfunction "-_-") (pintype "passive"))
      (node (ref "C63") (pin "2") (pinfunction "2_2") (pintype "passive"))
      (node (ref "C65") (pin "1") (pinfunction "1_1") (pintype "passive"))
      (node (ref "C66") (pin "2") (pinfunction "2_2") (pintype "passive"))
      (node (ref "C68") (pin "1") (pinfunction "1_1") (pintype "passive"))
      (node (ref "C70") (pin "2") (pinfunction "2_2") (pintype "passive"))
      (node (ref "C71") (pin "1") (pinfunction "1_1") (pintype "passive"))
      (node (ref "C9") (pin "2") (pinfunction "2_2") (pintype "passive"))
      (node (ref "CH1_IN+") (pin "1") (pinfunction "1_1") (pintype "bidirectional"))
      (node (ref "CH1_IN+") (pin "5") (pinfunction "5_5") (pintype "bidirectional"))
      (node (ref "CH1_IN-") (pin "1") (pinfunction "1_1") (pintype "bidirectional"))
      (node (ref "CH1_IN-") (pin "5") (pinfunction "5_5") (pintype "bidirectional"))
      (node (ref "CH2_IN+") (pin "1") (pinfunction "1_1") (pintype "bidirectional"))
      (node (ref "CH2_IN+") (pin "5") (pinfunction "5_5") (pintype "bidirectional"))
      (node (ref "CH2_IN-") (pin "1") (pinfunction "1_1") (pintype "bidirectional"))
      (node (ref "CH2_IN-") (pin "5") (pinfunction "5_5") (pintype "bidirectional"))
      (node (ref "D1") (pin "1") (pinfunction "A_1") (pintype "passive"))
      (node (ref "D2") (pin "1") (pinfunction "A_1") (pintype "passive"))
      (node (ref "D3") (pin "1") (pinfunction "A_1") (pintype "passive"))
      (node (ref "D4") (pin "1") (pinfunction "A_1") (pintype "passive"))
      (node (ref "D5") (pin "1") (pinfunction "A_1") (pintype "passive"))
      (node (ref "DRL") (pin "1") (pinfunction "1_1") (pintype "bidirectional"))
      (node (ref "DRL") (pin "5") (pinfunction "5_5") (pintype "bidirectional"))
      (node (ref "EXTMOD") (pin "10") (pinfunction "S_10") (pintype "passive"))
      (node (ref "EXTMOD") (pin "12") (pinfunction "S_12") (pintype "passive"))
      (node (ref "EXTMOD") (pin "6") (pinfunction "S_6") (pintype "passive"))
      (node (ref "EXTMOD") (pin "8") (pinfunction "S_8") (pintype "passive"))
      (node (ref "IC1") (pin "4") (pinfunction "V-_4") (pintype "power_in"))
      (node (ref "IC2") (pin "4") (pinfunction "V-_4") (pintype "power_in"))
      (node (ref "IC3") (pin "4") (pinfunction "V-_4") (pintype "power_in"))
      (node (ref "IC4") (pin "4") (pinfunction "V-_4") (pintype "power_in"))
      (node (ref "IC5") (pin "4") (pinfunction "V-_4") (pintype "power_in"))
      (node (ref "IC6") (pin "4") (pinfunction "V-_4") (pintype "power_in"))
      (node (ref "PGS1") (pin "1") (pinfunction "1_1") (pintype "input"))
      (node (ref "PGS2") (pin "2") (pinfunction "2_2") (pintype "input"))
      (node (ref "PGS3") (pin "1") (pinfunction "1_1") (pintype "input"))
      (node (ref "PGS4") (pin "2") (pinfunction "2_2") (pintype "input"))
      (node (ref "PGS5") (pin "1") (pinfunction "1_1") (pintype "input"))
      (node (ref "R5") (pin "1") (pinfunction "1_1") (pintype "passive"))
      (node (ref "R52") (pin "1") (pinfunction "1_1") (pintype "passive"))
      (node (ref "R7") (pin "1") (pinfunction "1_1") (pintype "passive"))
      (node (ref "SR1") (pin "3") (pinfunction "A_3") (pintype "input"))
      (node (ref "TR3") (pin "3") (pinfunction "3_3") (pintype "passive"))
      (node (ref "U1") (pin "28") (pinfunction "AGND_28") (pintype "power_in"))
      (node (ref "Z1") (pin "2") (pinfunction "A_2") (pintype "passive"))
    )
    (net (code "15") (name "Net-(C55-Pad2)") (class "Default")
      (node (ref "C55") (pin "2") (pinfunction "2_2") (pintype "passive"))
      (node (ref "R42") (pin "1") (pinfunction "1_1") (pintype "passive"))
      (node (ref "R44") (pin "1") (pinfunction "1_1") (pintype "passive"))
    )
    (net (code "16") (name "Net-(C56-Pad2)") (class "Default")
      (node (ref "C56") (pin "2") (pinfunction "2_2") (pintype "passive"))
      (node (ref "R43") (pin "1") (pinfunction "1_1") (pintype "passive"))
      (node (ref "R45") (pin "1") (pinfunction "1_1") (pintype "passive"))
    )
    (net (code "17") (name "Net-(C57-Pad1)") (class "Default")
      (node (ref "C57") (pin "1") (pinfunction "1_1") (pintype "passive"))
      (node (ref "R44") (pin "2") (pinfunction "2_2") (pintype "passive"))
      (node (ref "R46") (pin "1") (pinfunction "1_1") (pintype "passive"))
    )
    (net (code "18") (name "Net-(C58-Pad1)") (class "Default")
      (node (ref "C58") (pin "1") (pinfunction "1_1") (pintype "passive"))
      (node (ref "R45") (pin "2") (pinfunction "2_2") (pintype "passive"))
      (node (ref "R47") (pin "1") (pinfunction "1_1") (pintype "passive"))
    )
    (net (code "19") (name "Net-(CH1_IN+-Pad2)") (class "Default")
      (node (ref "CH1_IN+") (pin "2") (pinfunction "2_2") (pintype "bidirectional"))
      (node (ref "R58") (pin "1") (pinfunction "1_1") (pintype "passive"))
    )
    (net (code "20") (name "Net-(CH1_IN--Pad2)") (class "Default")
      (node (ref "CH1_IN-") (pin "2") (pinfunction "2_2") (pintype "bidirectional"))
      (node (ref "R57") (pin "1") (pinfunction "1_1") (pintype "passive"))
    )
    (net (code "21") (name "Net-(CH2_IN+-Pad2)") (class "Default")
      (node (ref "CH2_IN+") (pin "2") (pinfunction "2_2") (pintype "bidirectional"))
      (node (ref "R60") (pin "1") (pinfunction "1_1") (pintype "passive"))
    )
    (net (code "22") (name "Net-(CH2_IN--Pad2)") (class "Default")
      (node (ref "CH2_IN-") (pin "2") (pinfunction "2_2") (pintype "bidirectional"))
      (node (ref "R59") (pin "1") (pinfunction "1_1") (pintype "passive"))
    )
    (net (code "23") (name "Net-(COM-PP)") (class "Default")
      (node (ref "C43") (pin "1") (pinfunction "1_1") (pintype "passive"))
      (node (ref "COM") (pin "P$1") (pinfunction "PP_P$1") (pintype "passive"))
      (node (ref "EXTMOD") (pin "1") (pinfunction "S_1") (pintype "passive"))
      (node (ref "IC4") (pin "6") (pinfunction "-IN_6") (pintype "input"))
      (node (ref "R33") (pin "1") (pinfunction "1_1") (pintype "passive"))
      (node (ref "R34") (pin "1") (pinfunction "1_1") (pintype "passive"))
    )
    (net (code "24") (name "Net-(COMMODA-S)") (class "Default")
      (node (ref "COMMOD") (pin "1") (pinfunction "S_1") (pintype "passive"))
      (node (ref "U1") (pin "9") (pinfunction "(RXD)PD0_9") (pintype "bidirectional"))
    )
    (net (code "25") (name "Net-(COMMODC-S)") (class "Default")
      (node (ref "COMMOD") (pin "3") (pinfunction "S_3") (pintype "passive"))
      (node (ref "U1") (pin "10") (pinfunction "(TXD)PD1_10") (pintype "bidirectional"))
    )
    (net (code "26") (name "Net-(D1-AK)") (class "Default")
      (node (ref "C37") (pin "2") (pinfunction "2_2") (pintype "passive"))
      (node (ref "C39") (pin "2") (pinfunction "2_2") (pintype "passive"))
      (node (ref "D1") (pin "3") (pinfunction "AK_3") (pintype "passive"))
      (node (ref "R21") (pin "2") (pinfunction "2_2") (pintype "passive"))
      (node (ref "R23") (pin "2") (pinfunction "2_2") (pintype "passive"))
      (node (ref "R8") (pin "2") (pinfunction "2_2") (pintype "passive"))
    )
    (net (code "27") (name "Net-(D2-AK)") (class "Default")
      (node (ref "C37") (pin "1") (pinfunction "1_1") (pintype "passive"))
      (node (ref "C40") (pin "1") (pinfunction "1_1") (pintype "passive"))
      (node (ref "D2") (pin "3") (pinfunction "AK_3") (pintype "passive"))
      (node (ref "R22") (pin "2") (pinfunction "2_2") (pintype "passive"))
      (node (ref "R26") (pin "2") (pinfunction "2_2") (pintype "passive"))
      (node (ref "R53") (pin "2") (pinfunction "2_2") (pintype "passive"))
    )
    (net (code "28") (name "Net-(D3-AK)") (class "Default")
      (node (ref "C38") (pin "2") (pinfunction "2_2") (pintype "passive"))
      (node (ref "C41") (pin "2") (pinfunction "2_2") (pintype "passive"))
      (node (ref "D3") (pin "3") (pinfunction "AK_3") (pintype "passive"))
      (node (ref "R27") (pin "2") (pinfunction "2_2") (pintype "passive"))
      (node (ref "R29") (pin "2") (pinfunction "2_2") (pintype "passive"))
      (node (ref "R54") (pin "2") (pinfunction "2_2") (pintype "passive"))
    )
    (net (code "29") (name "Net-(D4-AK)") (class "Default")
      (node (ref "C38") (pin "1") (pinfunction "1_1") (pintype "passive"))
      (node (ref "C42") (pin "1") (pinfunction "1_1") (pintype "passive"))
      (node (ref "D4") (pin "3") (pinfunction "AK_3") (pintype "passive"))
      (node (ref "R28") (pin "2") (pinfunction "2_2") (pintype "passive"))
      (node (ref "R32") (pin "2") (pinfunction "2_2") (pintype "passive"))
      (node (ref "R55") (pin "2") (pinfunction "2_2") (pintype "passive"))
    )
    (net (code "30") (name "Net-(D5-AK)") (class "Default")
      (node (ref "C43") (pin "2") (pinfunction "2_2") (pintype "passive"))
      (node (ref "C44") (pin "2") (pinfunction "2_2") (pintype "passive"))
      (node (ref "D5") (pin "3") (pinfunction "AK_3") (pintype "passive"))
      (node (ref "R35") (pin "1") (pinfunction "1_1") (pintype "passive"))
      (node (ref "R56") (pin "2") (pinfunction "2_2") (pintype "passive"))
    )
    (net (code "31") (name "Net-(EXTMODC-S)") (class "Default")
      (node (ref "EXTMOD") (pin "11") (pinfunction "S_11") (pintype "passive"))
      (node (ref "R15") (pin "2") (pinfunction "2_2") (pintype "passive"))
    )
    (net (code "32") (name "Net-(EXTMODE-S)") (class "Default")
      (node (ref "EXTMOD") (pin "13") (pinfunction "S_13") (pintype "passive"))
      (node (ref "R63") (pin "2") (pinfunction "2_2") (pintype "passive"))
    )
    (net (code "33") (name "Net-(EXTMODH-S)") (class "Default")
      (node (ref "EXTMOD") (pin "3") (pinfunction "S_3") (pintype "passive"))
      (node (ref "R11") (pin "2") (pinfunction "2_2") (pintype "passive"))
    )
    (net (code "34") (name "Net-(EXTMODJ-S)") (class "Default")
      (node (ref "EXTMOD") (pin "5") (pinfunction "S_5") (pintype "passive"))
      (node (ref "R12") (pin "2") (pinfunction "2_2") (pintype "passive"))
    )
    (net (code "35") (name "Net-(EXTMODL-S)") (class "Default")
      (node (ref "EXTMOD") (pin "7") (pinfunction "S_7") (pintype "passive"))
      (node (ref "R13") (pin "2") (pinfunction "2_2") (pintype "passive"))
    )
    (net (code "36") (name "Net-(EXTMODN-S)") (class "Default")
      (node (ref "EXTMOD") (pin "9") (pinfunction "S_9") (pintype "passive"))
      (node (ref "R14") (pin "2") (pinfunction "2_2") (pintype "passive"))
    )
    (net (code "37") (name "Net-(GND_CAL-PP)") (class "Default")
      (node (ref "GND_CAL") (pin "P$1") (pinfunction "PP_P$1") (pintype "passive"))
      (node (ref "R18") (pin "1") (pinfunction "1_1") (pintype "passive"))
    )
    (net (code "38") (name "Net-(IC1A-+IN)") (class "Default")
      (node (ref "C51") (pin "2") (pinfunction "2_2") (pintype "passive"))
      (node (ref "IC1") (pin "3") (pinfunction "+IN_3") (pintype "input"))
      (node (ref "R36") (pin "1") (pinfunction "1_1") (pintype "passive"))
    )
    (net (code "39") (name "Net-(IC1A--IN)") (class "Default")
      (node (ref "C53") (pin "1") (pinfunction "1_1") (pintype "passive"))
      (node (ref "IC1") (pin "2") (pinfunction "-IN_2") (pintype "input"))
      (node (ref "R38") (pin "1") (pinfunction "1_1") (pintype "passive"))
      (node (ref "R40") (pin "1") (pinfunction "1_1") (pintype "passive"))
    )
    (net (code "40") (name "Net-(IC1A-OUT)") (class "Default")
      (node (ref "C53") (pin "2") (pinfunction "2_2") (pintype "passive"))
      (node (ref "C55") (pin "1") (pinfunction "1_1") (pintype "passive"))
      (node (ref "IC1") (pin "1") (pinfunction "OUT_1") (pintype "output"))
      (node (ref "R38") (pin "2") (pinfunction "2_2") (pintype "passive"))
    )
    (net (code "41") (name "Net-(IC1B-+IN)") (class "Default")
      (node (ref "C59") (pin "1") (pinfunction "1_1") (pintype "passive"))
      (node (ref "IC1") (pin "5") (pinfunction "+IN_5") (pintype "input"))
      (node (ref "R46") (pin "2") (pinfunction "2_2") (pintype "passive"))
    )
    (net (code "42") (name "Net-(IC1B--IN)") (class "Default")
      (node (ref "C61") (pin "1") (pinfunction "1_1") (pintype "passive"))
      (node (ref "IC1") (pin "6") (pinfunction "-IN_6") (pintype "input"))
      (node (ref "R48") (pin "1") (pinfunction "1_1") (pintype "passive"))
      (node (ref "R50") (pin "1") (pinfunction "1_1") (pintype "passive"))
    )
    (net (code "43") (name "Net-(IC1B-OUT)") (class "Default")
      (node (ref "C57") (pin "2") (pinfunction "2_2") (pintype "passive"))
      (node (ref "C61") (pin "2") (pinfunction "2_2") (pintype "passive"))
      (node (ref "IC1") (pin "7") (pinfunction "OUT_7") (pintype "output"))
      (node (ref "R10") (pin "2") (pinfunction "2_2") (pintype "passive"))
      (node (ref "R50") (pin "2") (pinfunction "2_2") (pintype "passive"))
    )
    (net (code "44") (name "Net-(IC2A-+IN)") (class "Default")
      (node (ref "C52") (pin "2") (pinfunction "2_2") (pintype "passive"))
      (node (ref "IC2") (pin "3") (pinfunction "+IN_3") (pintype "input"))
      (node (ref "R37") (pin "1") (pinfunction "1_1") (pintype "passive"))
    )
    (net (code "45") (name "Net-(IC2A--IN)") (class "Default")
      (node (ref "C54") (pin "1") (pinfunction "1_1") (pintype "passive"))
      (node (ref "IC2") (pin "2") (pinfunction "-IN_2") (pintype "input"))
      (node (ref "R39") (pin "1") (pinfunction "1_1") (pintype "passive"))
      (node (ref "R41") (pin "1") (pinfunction "1_1") (pintype "passive"))
    )
    (net (code "46") (name "Net-(IC2A-OUT)") (class "Default")
      (node (ref "C54") (pin "2") (pinfunction "2_2") (pintype "passive"))
      (node (ref "C56") (pin "1") (pinfunction "1_1") (pintype "passive"))
      (node (ref "IC2") (pin "1") (pinfunction "OUT_1") (pintype "output"))
      (node (ref "R39") (pin "2") (pinfunction "2_2") (pintype "passive"))
    )
    (net (code "47") (name "Net-(IC2B-+IN)") (class "Default")
      (node (ref "C60") (pin "1") (pinfunction "1_1") (pintype "passive"))
      (node (ref "IC2") (pin "5") (pinfunction "+IN_5") (pintype "input"))
      (node (ref "R47") (pin "2") (pinfunction "2_2") (pintype "passive"))
    )
    (net (code "48") (name "Net-(IC2B--IN)") (class "Default")
      (node (ref "C62") (pin "1") (pinfunction "1_1") (pintype "passive"))
      (node (ref "IC2") (pin "6") (pinfunction "-IN_6") (pintype "input"))
      (node (ref "R49") (pin "1") (pinfunction "1_1") (pintype "passive"))
      (node (ref "R51") (pin "1") (pinfunction "1_1") (pintype "passive"))
    )
    (net (code "49") (name "Net-(IC2B-OUT)") (class "Default")
      (node (ref "C58") (pin "2") (pinfunction "2_2") (pintype "passive"))
      (node (ref "C62") (pin "2") (pinfunction "2_2") (pintype "passive"))
      (node (ref "IC2") (pin "7") (pinfunction "OUT_7") (pintype "output"))
      (node (ref "R51") (pin "2") (pinfunction "2_2") (pintype "passive"))
      (node (ref "R9") (pin "2") (pinfunction "2_2") (pintype "passive"))
    )
    (net (code "50") (name "Net-(IC3A-+IN)") (class "Default")
      (node (ref "IC3") (pin "3") (pinfunction "+IN_3") (pintype "input"))
      (node (ref "R30") (pin "2") (pinfunction "2_2") (pintype "passive"))
      (node (ref "R31") (pin "2") (pinfunction "2_2") (pintype "passive"))
    )
    (net (code "51") (name "Net-(IC3A--IN)") (class "Default")
      (node (ref "IC3") (pin "1") (pinfunction "OUT_1") (pintype "output"))
      (node (ref "IC3") (pin "2") (pinfunction "-IN_2") (pintype "input"))
      (node (ref "R34") (pin "2") (pinfunction "2_2") (pintype "passive"))
    )
    (net (code "52") (name "Net-(IC3B-+IN)") (class "Default")
      (node (ref "IC3") (pin "5") (pinfunction "+IN_5") (pintype "input"))
      (node (ref "R24") (pin "2") (pinfunction "2_2") (pintype "passive"))
      (node (ref "R25") (pin "2") (pinfunction "2_2") (pintype "passive"))
    )
    (net (code "53") (name "Net-(IC3B--IN)") (class "Default")
      (node (ref "IC3") (pin "6") (pinfunction "-IN_6") (pintype "input"))
      (node (ref "IC3") (pin "7") (pinfunction "OUT_7") (pintype "output"))
      (node (ref "R33") (pin "2") (pinfunction "2_2") (pintype "passive"))
    )
    (net (code "54") (name "Net-(IC4B-+IN)") (class "Default")
      (node (ref "IC4") (pin "5") (pinfunction "+IN_5") (pintype "input"))
      (node (ref "TR3") (pin "2") (pinfunction "2_2") (pintype "passive"))
      (node (ref "TR3_DIS") (pin "1") (pinfunction "1_1") (pintype "passive"))
    )
    (net (code "55") (name "Net-(IC4B-OUT)") (class "Default")
      (node (ref "C44") (pin "1") (pinfunction "1_1") (pintype "passive"))
      (node (ref "IC4") (pin "7") (pinfunction "OUT_7") (pintype "output"))
      (node (ref "R35") (pin "2") (pinfunction "2_2") (pintype "passive"))
    )
    (net (code "56") (name "Net-(IC5-+IN)") (class "Default")
      (node (ref "IC5") (pin "3") (pinfunction "+IN_3") (pintype "input"))
      (node (ref "R26") (pin "1") (pinfunction "1_1") (pintype "passive"))
    )
    (net (code "57") (name "Net-(IC5--IN)") (class "Default")
      (node (ref "IC5") (pin "2") (pinfunction "-IN_2") (pintype "input"))
      (node (ref "R23") (pin "1") (pinfunction "1_1") (pintype "passive"))
    )
    (net (code "58") (name "Net-(IC5-OUT)") (class "Default")
      (node (ref "C51") (pin "1") (pinfunction "1_1") (pintype "passive"))
      (node (ref "IC5") (pin "6") (pinfunction "OUT_6") (pintype "output"))
    )
    (net (code "59") (name "Net-(IC5-RG-Pad1)") (class "Default")
      (node (ref "IC5") (pin "1") (pinfunction "RG_1") (pintype "passive"))
      (node (ref "R24") (pin "1") (pinfunction "1_1") (pintype "passive"))
    )
    (net (code "60") (name "Net-(IC5-RG-Pad8)") (class "Default")
      (node (ref "IC5") (pin "8") (pinfunction "RG_8") (pintype "passive"))
      (node (ref "R25") (pin "1") (pinfunction "1_1") (pintype "passive"))
    )
    (net (code "61") (name "Net-(IC6-+IN)") (class "Default")
      (node (ref "IC6") (pin "3") (pinfunction "+IN_3") (pintype "input"))
      (node (ref "R32") (pin "1") (pinfunction "1_1") (pintype "passive"))
    )
    (net (code "62") (name "Net-(IC6--IN)") (class "Default")
      (node (ref "IC6") (pin "2") (pinfunction "-IN_2") (pintype "input"))
      (node (ref "R29") (pin "1") (pinfunction "1_1") (pintype "passive"))
    )
    (net (code "63") (name "Net-(IC6-OUT)") (class "Default")
      (node (ref "C52") (pin "1") (pinfunction "1_1") (pintype "passive"))
      (node (ref "IC6") (pin "6") (pinfunction "OUT_6") (pintype "output"))
    )
    (net (code "64") (name "Net-(IC6-RG-Pad1)") (class "Default")
      (node (ref "IC6") (pin "1") (pinfunction "RG_1") (pintype "passive"))
      (node (ref "R30") (pin "1") (pinfunction "1_1") (pintype "passive"))
    )
    (net (code "65") (name "Net-(IC6-RG-Pad8)") (class "Default")
      (node (ref "IC6") (pin "8") (pinfunction "RG_8") (pintype "passive"))
      (node (ref "R31") (pin "1") (pinfunction "1_1") (pintype "passive"))
    )
    (net (code "66") (name "Net-(PROGRAMA-S)") (class "Default")
      (node (ref "PROGRAM") (pin "1") (pinfunction "S_1") (pintype "passive"))
      (node (ref "U1") (pin "2") (pinfunction "(MISO)PB6_2") (pintype "bidirectional"))
    )
    (net (code "67") (name "Net-(PROGRAMC-S)") (class "Default")
      (node (ref "PROGRAM") (pin "3") (pinfunction "S_3") (pintype "passive"))
      (node (ref "U1") (pin "3") (pinfunction "(SCK)PB7_3") (pintype "bidirectional"))
    )
    (net (code "68") (name "Net-(PROGRAMD-S)") (class "Default")
      (node (ref "PROGRAM") (pin "4") (pinfunction "S_4") (pintype "passive"))
      (node (ref "U1") (pin "1") (pinfunction "(MOSI)PB5_1") (pintype "bidirectional"))
    )
    (net (code "69") (name "Net-(PWR-C)") (class "Default")
      (node (ref "PWR") (pin "K") (pinfunction "C_K") (pintype "passive"))
      (node (ref "R62") (pin "2") (pinfunction "2_2") (pintype "passive"))
    )
    (net (code "70") (name "Net-(R16-Pad2)") (class "Default")
      (node (ref "R16") (pin "2") (pinfunction "2_2") (pintype "passive"))
      (node (ref "R17") (pin "2") (pinfunction "2_2") (pintype "passive"))
      (node (ref "R19") (pin "1") (pinfunction "1_1") (pintype "passive"))
    )
    (net (code "71") (name "Net-(R19-Pad2)") (class "Default")
      (node (ref "R19") (pin "2") (pinfunction "2_2") (pintype "passive"))
      (node (ref "R20") (pin "1") (pinfunction "1_1") (pintype "passive"))
    )
    (net (code "72") (name "Net-(R40-Pad2)") (class "Default")
      (node (ref "R40") (pin "2") (pinfunction "2_2") (pintype "passive"))
      (node (ref "TR1") (pin "1") (pinfunction "1_1") (pintype "passive"))
    )
    (net (code "73") (name "Net-(R41-Pad2)") (class "Default")
      (node (ref "R41") (pin "2") (pinfunction "2_2") (pintype "passive"))
      (node (ref "TR2") (pin "1") (pinfunction "1_1") (pintype "passive"))
    )
    (net (code "74") (name "Net-(SR1-R)") (class "Default")
      (node (ref "R4") (pin "1") (pinfunction "1_1") (pintype "passive"))
      (node (ref "R5") (pin "2") (pinfunction "2_2") (pintype "passive"))
      (node (ref "SR1") (pin "2") (pinfunction "R_2") (pintype "input"))
    )
    (net (code "75") (name "Net-(TCK-PP)") (class "Default")
      (node (ref "TCK") (pin "P$1") (pinfunction "PP_P$1") (pintype "passive"))
      (node (ref "U1") (pin "21") (pinfunction "PC2(TCK)_21") (pintype "bidirectional"))
    )
    (net (code "76") (name "Net-(TDI-PP)") (class "Default")
      (node (ref "TDI") (pin "P$1") (pinfunction "PP_P$1") (pintype "passive"))
      (node (ref "U1") (pin "24") (pinfunction "PC5(TDI)_24") (pintype "bidirectional"))
    )
    (net (code "77") (name "Net-(TDO-PP)") (class "Default")
      (node (ref "TDO") (pin "P$1") (pinfunction "PP_P$1") (pintype "passive"))
      (node (ref "U1") (pin "23") (pinfunction "PC4(TDO)_23") (pintype "bidirectional"))
    )
    (net (code "78") (name "Net-(TMS-PP)") (class "Default")
      (node (ref "TMS") (pin "P$1") (pinfunction "PP_P$1") (pintype "passive"))
      (node (ref "U1") (pin "22") (pinfunction "PC3(TMS)_22") (pintype "bidirectional"))
    )
    (net (code "79") (name "Net-(U1-(ADC2)PA2)") (class "Default")
      (node (ref "C17") (pin "1") (pinfunction "1_1") (pintype "passive"))
      (node (ref "R63") (pin "1") (pinfunction "1_1") (pintype "passive"))
      (node (ref "U1") (pin "35") (pinfunction "(ADC2)PA2_35") (pintype "bidirectional"))
    )
    (net (code "80") (name "Net-(U1-(ADC3)PA3)") (class "Default")
      (node (ref "C16") (pin "1") (pinfunction "1_1") (pintype "passive"))
      (node (ref "R15") (pin "1") (pinfunction "1_1") (pintype "passive"))
      (node (ref "U1") (pin "34") (pinfunction "(ADC3)PA3_34") (pintype "bidirectional"))
    )
    (net (code "81") (name "Net-(U1-(ADC4)PA4)") (class "Default")
      (node (ref "C15") (pin "1") (pinfunction "1_1") (pintype "passive"))
      (node (ref "R14") (pin "1") (pinfunction "1_1") (pintype "passive"))
      (node (ref "U1") (pin "33") (pinfunction "(ADC4)PA4_33") (pintype "bidirectional"))
    )
    (net (code "82") (name "Net-(U1-(ADC5)PA5)") (class "Default")
      (node (ref "C14") (pin "1") (pinfunction "1_1") (pintype "passive"))
      (node (ref "R13") (pin "1") (pinfunction "1_1") (pintype "passive"))
      (node (ref "U1") (pin "32") (pinfunction "(ADC5)PA5_32") (pintype "bidirectional"))
    )
    (net (code "83") (name "Net-(U1-(ADC6)PA6)") (class "Default")
      (node (ref "C12") (pin "1") (pinfunction "1_1") (pintype "passive"))
      (node (ref "R12") (pin "1") (pinfunction "1_1") (pintype "passive"))
      (node (ref "U1") (pin "31") (pinfunction "(ADC6)PA6_31") (pintype "bidirectional"))
    )
    (net (code "84") (name "Net-(U1-(ADC7)PA7)") (class "Default")
      (node (ref "C11") (pin "1") (pinfunction "1_1") (pintype "passive"))
      (node (ref "R11") (pin "1") (pinfunction "1_1") (pintype "passive"))
      (node (ref "U1") (pin "30") (pinfunction "(ADC7)PA7_30") (pintype "bidirectional"))
    )
    (net (code "85") (name "Net-(U1-AVCC)") (class "Default")
      (node (ref "C4") (pin "1") (pinfunction "1_1") (pintype "passive"))
      (node (ref "R2") (pin "1") (pinfunction "1_1") (pintype "passive"))
      (node (ref "U1") (pin "27") (pinfunction "AVCC_27") (pintype "power_in"))
    )
    (net (code "86") (name "Net-(U1-XTAL1)") (class "Default")
      (node (ref "C3") (pin "1") (pinfunction "1_1") (pintype "passive"))
      (node (ref "Q1") (pin "2") (pinfunction "2_2") (pintype "passive"))
      (node (ref "U1") (pin "8") (pinfunction "XTAL1_8") (pintype "bidirectional"))
    )
    (net (code "87") (name "Net-(U1-XTAL2)") (class "Default")
      (node (ref "C2") (pin "1") (pinfunction "1_1") (pintype "passive"))
      (node (ref "Q1") (pin "1") (pinfunction "1_1") (pintype "passive"))
      (node (ref "U1") (pin "7") (pinfunction "XTAL2_7") (pintype "bidirectional"))
    )
    (net (code "88") (name "Net-(V_CAL-PP)") (class "Default")
      (node (ref "R16") (pin "1") (pinfunction "1_1") (pintype "passive"))
      (node (ref "V_CAL") (pin "P$1") (pinfunction "PP_P$1") (pintype "passive"))
    )
    (net (code "89") (name "PE") (class "Default")
      (node (ref "C1") (pin "2") (pinfunction "2_2") (pintype "passive"))
      (node (ref "C2") (pin "2") (pinfunction "2_2") (pintype "passive"))
      (node (ref "C24") (pin "2") (pinfunction "2_2") (pintype "passive"))
      (node (ref "C25") (pin "2") (pinfunction "2_2") (pintype "passive"))
      (node (ref "C26") (pin "-") (pinfunction "-_-") (pintype "passive"))
      (node (ref "C3") (pin "2") (pinfunction "2_2") (pintype "passive"))
      (node (ref "C7") (pin "2") (pinfunction "2_2") (pintype "passive"))
      (node (ref "C72") (pin "2") (pinfunction "2_2") (pintype "passive"))
      (node (ref "C8") (pin "2") (pinfunction "2_2") (pintype "passive"))
      (node (ref "COMMOD") (pin "2") (pinfunction "S_2") (pintype "passive"))
      (node (ref "COMMOD") (pin "4") (pinfunction "S_4") (pintype "passive"))
      (node (ref "POW") (pin "GND") (pinfunction "GND_GND") (pintype "bidirectional"))
      (node (ref "PROGRAM") (pin "6") (pinfunction "S_6") (pintype "passive"))
      (node (ref "R52") (pin "2") (pinfunction "2_2") (pintype "passive"))
      (node (ref "R62") (pin "1") (pinfunction "1_1") (pintype "passive"))
      (node (ref "U1") (pin "18") (pinfunction "GND1_18") (pintype "bidirectional"))
      (node (ref "U1") (pin "39") (pinfunction "GND2_39") (pintype "bidirectional"))
      (node (ref "U1") (pin "6") (pinfunction "GND_6") (pintype "power_in"))
    )
    (net (code "90") (name "VIN") (class "Default")
      (node (ref "L2") (pin "1") (pinfunction "1_1") (pintype "passive"))
      (node (ref "POW") (pin "VCC") (pinfunction "VCC_VCC") (pintype "bidirectional"))
      (node (ref "PWR") (pin "A") (pinfunction "A_A") (pintype "passive"))
    )
    (net (code "91") (name "V_REF") (class "Default")
      (node (ref "C30") (pin "1") (pinfunction "1_1") (pintype "passive"))
      (node (ref "C31") (pin "1") (pinfunction "1_1") (pintype "passive"))
      (node (ref "C32") (pin "+") (pinfunction "+_+") (pintype "passive"))
      (node (ref "C46") (pin "2") (pinfunction "2_2") (pintype "passive"))
      (node (ref "C47") (pin "2") (pinfunction "2_2") (pintype "passive"))
      (node (ref "C49") (pin "2") (pinfunction "2_2") (pintype "passive"))
      (node (ref "C50") (pin "2") (pinfunction "2_2") (pintype "passive"))
      (node (ref "C59") (pin "2") (pinfunction "2_2") (pintype "passive"))
      (node (ref "C60") (pin "2") (pinfunction "2_2") (pintype "passive"))
      (node (ref "C64") (pin "2") (pinfunction "2_2") (pintype "passive"))
      (node (ref "C65") (pin "2") (pinfunction "2_2") (pintype "passive"))
      (node (ref "C67") (pin "2") (pinfunction "2_2") (pintype "passive"))
      (node (ref "C68") (pin "2") (pinfunction "2_2") (pintype "passive"))
      (node (ref "C69") (pin "2") (pinfunction "2_2") (pintype "passive"))
      (node (ref "C71") (pin "2") (pinfunction "2_2") (pintype "passive"))
      (node (ref "EXTMOD") (pin "14") (pinfunction "S_14") (pintype "passive"))
      (node (ref "IC4") (pin "1") (pinfunction "OUT_1") (pintype "output"))
      (node (ref "IC4") (pin "2") (pinfunction "-IN_2") (pintype "input"))
      (node (ref "IC5") (pin "5") (pinfunction "REF_5") (pintype "passive"))
      (node (ref "IC6") (pin "5") (pinfunction "REF_5") (pintype "passive"))
      (node (ref "R17") (pin "1") (pinfunction "1_1") (pintype "passive"))
      (node (ref "R18") (pin "2") (pinfunction "2_2") (pintype "passive"))
      (node (ref "R36") (pin "2") (pinfunction "2_2") (pintype "passive"))
      (node (ref "R37") (pin "2") (pinfunction "2_2") (pintype "passive"))
      (node (ref "R42") (pin "2") (pinfunction "2_2") (pintype "passive"))
      (node (ref "R43") (pin "2") (pinfunction "2_2") (pintype "passive"))
      (node (ref "R48") (pin "2") (pinfunction "2_2") (pintype "passive"))
      (node (ref "R49") (pin "2") (pinfunction "2_2") (pintype "passive"))
      (node (ref "R53") (pin "1") (pinfunction "1_1") (pintype "passive"))
      (node (ref "R54") (pin "1") (pinfunction "1_1") (pintype "passive"))
      (node (ref "R55") (pin "1") (pinfunction "1_1") (pintype "passive"))
      (node (ref "R8") (pin "1") (pinfunction "1_1") (pintype "passive"))
      (node (ref "TR1") (pin "2") (pinfunction "2_2") (pintype "passive"))
      (node (ref "TR1") (pin "3") (pinfunction "3_3") (pintype "passive"))
      (node (ref "TR2") (pin "2") (pinfunction "2_2") (pintype "passive"))
      (node (ref "TR2") (pin "3") (pinfunction "3_3") (pintype "passive"))
      (node (ref "TR3") (pin "1") (pinfunction "1_1") (pintype "passive"))
      (node (ref "TR3_DIS") (pin "2") (pinfunction "2_2") (pintype "passive"))
      (node (ref "VREF") (pin "P$1") (pinfunction "PP_P$1") (pintype "passive"))
    )
    (net (code "92") (name "unconnected-(CH1_IN+-Pad4)") (class "Default")
      (node (ref "CH1_IN+") (pin "4") (pinfunction "4_4") (pintype "bidirectional"))
    )
    (net (code "93") (name "unconnected-(CH1_IN--Pad4)") (class "Default")
      (node (ref "CH1_IN-") (pin "4") (pinfunction "4_4") (pintype "bidirectional"))
    )
    (net (code "94") (name "unconnected-(CH2_IN+-Pad4)") (class "Default")
      (node (ref "CH2_IN+") (pin "4") (pinfunction "4_4") (pintype "bidirectional"))
    )
    (net (code "95") (name "unconnected-(CH2_IN--Pad4)") (class "Default")
      (node (ref "CH2_IN-") (pin "4") (pinfunction "4_4") (pintype "bidirectional"))
    )
    (net (code "96") (name "unconnected-(COMMODE-S-Pad5)") (class "Default")
      (node (ref "COMMOD") (pin "5") (pinfunction "S_5") (pintype "passive"))
    )
    (net (code "97") (name "unconnected-(DRL-Pad2)") (class "Default")
      (node (ref "DRL") (pin "2") (pinfunction "2_2") (pintype "bidirectional"))
    )
    (net (code "98") (name "unconnected-(DRL-Pad4)") (class "Default")
      (node (ref "DRL") (pin "4") (pinfunction "4_4") (pintype "bidirectional"))
    )
    (net (code "99") (name "unconnected-(POW-PadD+)") (class "Default")
      (node (ref "POW") (pin "D+") (pinfunction "D+_D+") (pintype "bidirectional"))
    )
    (net (code "100") (name "unconnected-(POW-PadD-)") (class "Default")
      (node (ref "POW") (pin "D-") (pinfunction "D-_D-") (pintype "bidirectional"))
    )
    (net (code "101") (name "unconnected-(POW-PadID)") (class "Default")
      (node (ref "POW") (pin "ID") (pinfunction "ID_ID") (pintype "bidirectional"))
    )
    (net (code "102") (name "unconnected-(U1-(AIN0{slash}INT2)PB2-Pad42)") (class "Default")
      (node (ref "U1") (pin "42") (pinfunction "(AIN0/INT2)PB2_42") (pintype "bidirectional"))
    )
    (net (code "103") (name "unconnected-(U1-(AIN1)PB3-Pad43)") (class "Default")
      (node (ref "U1") (pin "43") (pinfunction "(AIN1)PB3_43") (pintype "bidirectional"))
    )
    (net (code "104") (name "unconnected-(U1-(ICP)PD6-Pad15)") (class "Default")
      (node (ref "U1") (pin "15") (pinfunction "(ICP)PD6_15") (pintype "bidirectional"))
    )
    (net (code "105") (name "unconnected-(U1-(INT0)PD2-Pad11)") (class "Default")
      (node (ref "U1") (pin "11") (pinfunction "(INT0)PD2_11") (pintype "bidirectional"))
    )
    (net (code "106") (name "unconnected-(U1-(INT1)PD3-Pad12)") (class "Default")
      (node (ref "U1") (pin "12") (pinfunction "(INT1)PD3_12") (pintype "bidirectional"))
    )
    (net (code "107") (name "unconnected-(U1-(OC1B)PD4-Pad13)") (class "Default")
      (node (ref "U1") (pin "13") (pinfunction "(OC1B)PD4_13") (pintype "bidirectional"))
    )
    (net (code "108") (name "unconnected-(U1-(OC2)PD7-Pad16)") (class "Default")
      (node (ref "U1") (pin "16") (pinfunction "(OC2)PD7_16") (pintype "bidirectional"))
    )
    (net (code "109") (name "unconnected-(U1-(SS)PB4-Pad44)") (class "Default")
      (node (ref "U1") (pin "44") (pinfunction "(SS)PB4_44") (pintype "bidirectional"))
    )
    (net (code "110") (name "unconnected-(U1-(T0)PB0-Pad40)") (class "Default")
      (node (ref "U1") (pin "40") (pinfunction "(T0)PB0_40") (pintype "bidirectional"))
    )
    (net (code "111") (name "unconnected-(U1-(T1)PB1-Pad41)") (class "Default")
      (node (ref "U1") (pin "41") (pinfunction "(T1)PB1_41") (pintype "bidirectional"))
    )
    (net (code "112") (name "unconnected-(U1-(TOSC1)PC6-Pad25)") (class "Default")
      (node (ref "U1") (pin "25") (pinfunction "(TOSC1)PC6_25") (pintype "bidirectional"))
    )
    (net (code "113") (name "unconnected-(U1-(TOSC2)PC7-Pad26)") (class "Default")
      (node (ref "U1") (pin "26") (pinfunction "(TOSC2)PC7_26") (pintype "bidirectional"))
    )
    (net (code "114") (name "unconnected-(U1-PC0(SCL)-Pad19)") (class "Default")
      (node (ref "U1") (pin "19") (pinfunction "PC0(SCL)_19") (pintype "bidirectional"))
    )
    (net (code "115") (name "unconnected-(U1-PC1(SDA)-Pad20)") (class "Default")
      (node (ref "U1") (pin "20") (pinfunction "PC1(SDA)_20") (pintype "bidirectional"))
    )
  )
)
